# fc_rocket.net
KiCad netlist of a schematic drawn in EAGLE
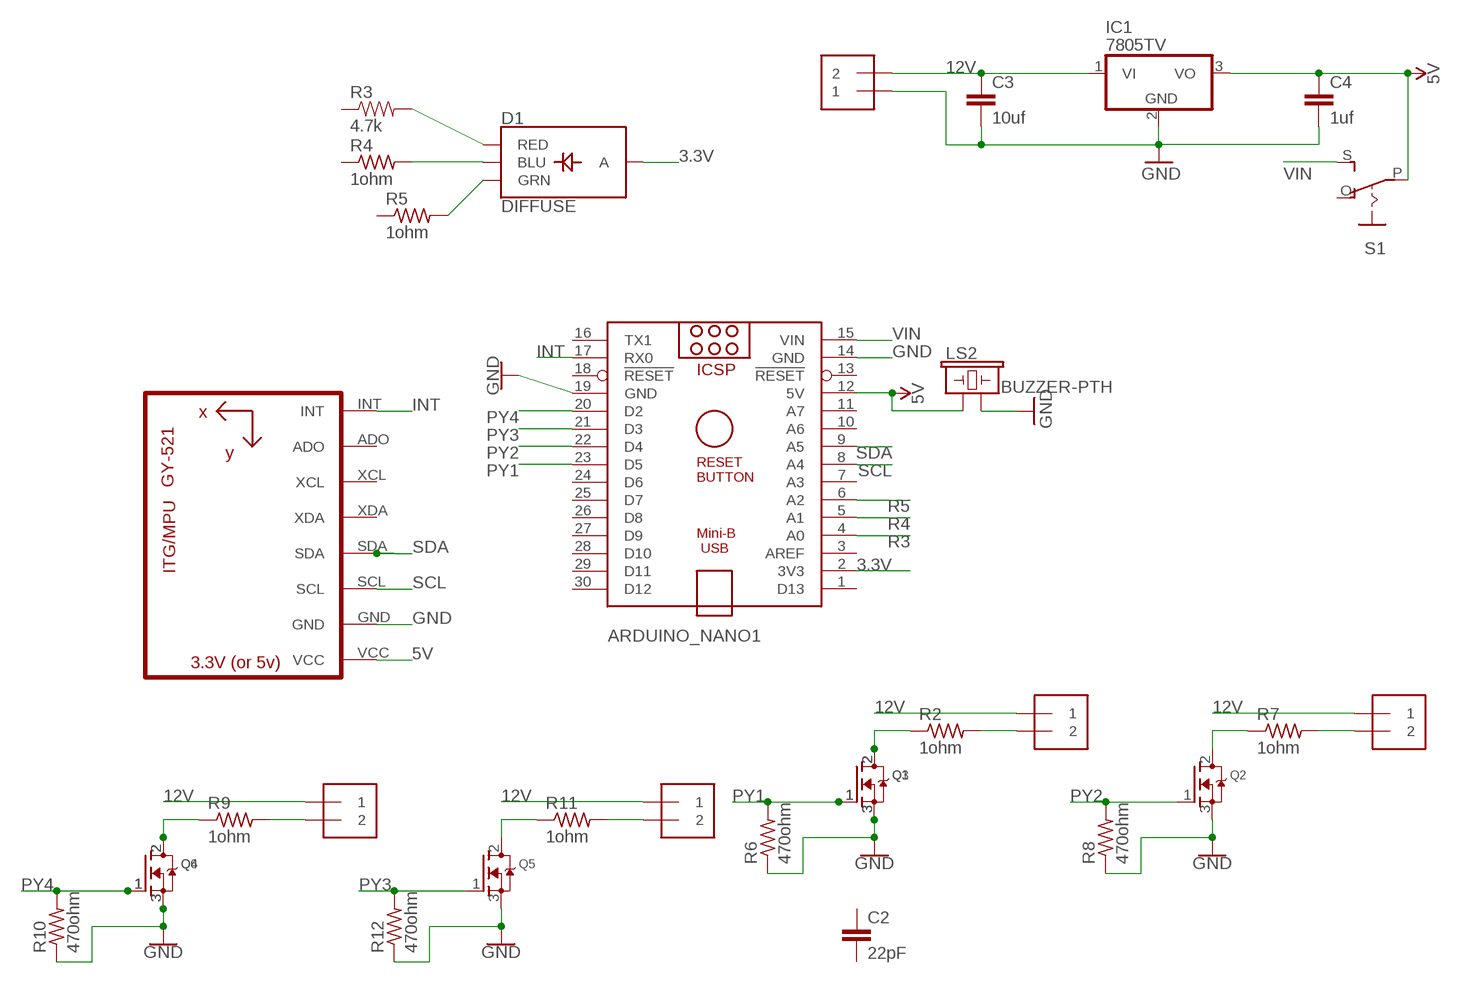
[diagram p0: schematic, sheet 1]

(export (version "E")
  (design (tool "Eeschema 10.0.6"))
  (components
    (comp (ref "ARDUINO_NANO1")
      (value "ARDUINO_NANO")
      (footprint "eagle-import:ARDUINO_NANO")
      (libsource (lib "eagle-import") (part "ARDUINO_NANO"))
    )
    (comp (ref "C2")
      (value "22pF")
      (footprint "eagle-import:CAP-PTH-2.54")
      (libsource (lib "eagle-import") (part "22PF-PTH-2.54MM-200V-5%"))
    )
    (comp (ref "C3")
      (value "10uf")
      (footprint "eagle-import:CAP-PTH-2.54")
      (libsource (lib "eagle-import") (part "22PF-PTH-2.54MM-200V-5%"))
    )
    (comp (ref "C4")
      (value "1uf")
      (footprint "eagle-import:CAP-PTH-2.54")
      (libsource (lib "eagle-import") (part "22PF-PTH-2.54MM-200V-5%"))
    )
    (comp (ref "D1")
      (value "DIFFUSE")
      (footprint "eagle-import:LED-RGB-THRU")
      (libsource (lib "eagle-import") (part "LED-RGB-CADIFFUSE"))
    )
    (comp (ref "IC1")
      (value "7805TV")
      (footprint "eagle-import:TO220V")
      (libsource (lib "eagle-import") (part "78TV05"))
    )
    (comp (ref "J2")
      (value "1X2-3.5MM")
      (footprint "eagle-import:1X2-3.5MM")
      (libsource (lib "eagle-import") (part "1X2-3.5MM"))
    )
    (comp (ref "J3")
      (value "1X2-3.5MM")
      (footprint "eagle-import:1X2-3.5MM")
      (libsource (lib "eagle-import") (part "1X2-3.5MM"))
    )
    (comp (ref "J4")
      (value "1X2-3.5MM")
      (footprint "eagle-import:1X2-3.5MM")
      (libsource (lib "eagle-import") (part "1X2-3.5MM"))
    )
    (comp (ref "J5")
      (value "1X2-3.5MM")
      (footprint "eagle-import:1X2-3.5MM")
      (libsource (lib "eagle-import") (part "1X2-3.5MM"))
    )
    (comp (ref "J6")
      (value "1X2-3.5MM")
      (footprint "eagle-import:1X2-3.5MM")
      (libsource (lib "eagle-import") (part "1X2-3.5MM"))
    )
    (comp (ref "LS2")
      (value "BUZZER-PTH")
      (footprint "eagle-import:BUZZER-12MM")
      (libsource (lib "eagle-import") (part "BUZZER-PTH"))
    )
    (comp (ref "Q1")
      (value "MOSFET-NGDS_TO220V")
      (footprint "eagle-import:TO220V")
      (libsource (lib "eagle-import") (part "MOSFET-NGDS_TO220V"))
    )
    (comp (ref "Q2")
      (value "MOSFET-NGDS_TO220V")
      (footprint "eagle-import:TO220V")
      (libsource (lib "eagle-import") (part "MOSFET-NGDS_TO220V"))
    )
    (comp (ref "Q3")
      (value "MOSFET-NGDS_TO220V")
      (footprint "eagle-import:TO220V")
      (libsource (lib "eagle-import") (part "MOSFET-NGDS_TO220V"))
    )
    (comp (ref "Q4")
      (value "MOSFET-NGDS_TO220V")
      (footprint "eagle-import:TO220V")
      (libsource (lib "eagle-import") (part "MOSFET-NGDS_TO220V"))
    )
    (comp (ref "Q5")
      (value "MOSFET-NGDS_TO220V")
      (footprint "eagle-import:TO220V")
      (libsource (lib "eagle-import") (part "MOSFET-NGDS_TO220V"))
    )
    (comp (ref "Q6")
      (value "MOSFET-NGDS_TO220V")
      (footprint "eagle-import:TO220V")
      (libsource (lib "eagle-import") (part "MOSFET-NGDS_TO220V"))
    )
    (comp (ref "R2")
      (value "1ohm")
      (footprint "eagle-import:0805-THM")
      (libsource (lib "eagle-import") (part "FLIPFLOP-RES"))
    )
    (comp (ref "R3")
      (value "4.7k")
      (footprint "eagle-import:0603")
      (libsource (lib "eagle-import") (part "4.7KOHM-0603-1/10W-1%"))
    )
    (comp (ref "R4")
      (value "1ohm")
      (footprint "eagle-import:0805-THM")
      (libsource (lib "eagle-import") (part "FLIPFLOP-RES"))
    )
    (comp (ref "R5")
      (value "1ohm")
      (footprint "eagle-import:0805-THM")
      (libsource (lib "eagle-import") (part "FLIPFLOP-RES"))
    )
    (comp (ref "R6")
      (value "470ohm")
      (footprint "eagle-import:0805-THM")
      (libsource (lib "eagle-import") (part "FLIPFLOP-RES"))
    )
    (comp (ref "R7")
      (value "1ohm")
      (footprint "eagle-import:0805-THM")
      (libsource (lib "eagle-import") (part "FLIPFLOP-RES"))
    )
    (comp (ref "R8")
      (value "470ohm")
      (footprint "eagle-import:0805-THM")
      (libsource (lib "eagle-import") (part "FLIPFLOP-RES"))
    )
    (comp (ref "R9")
      (value "1ohm")
      (footprint "eagle-import:0805-THM")
      (libsource (lib "eagle-import") (part "FLIPFLOP-RES"))
    )
    (comp (ref "R10")
      (value "470ohm")
      (footprint "eagle-import:0805-THM")
      (libsource (lib "eagle-import") (part "FLIPFLOP-RES"))
    )
    (comp (ref "R11")
      (value "1ohm")
      (footprint "eagle-import:0805-THM")
      (libsource (lib "eagle-import") (part "FLIPFLOP-RES"))
    )
    (comp (ref "R12")
      (value "470ohm")
      (footprint "eagle-import:0805-THM")
      (libsource (lib "eagle-import") (part "FLIPFLOP-RES"))
    )
    (comp (ref "S1")
      (value "EG1218S")
      (footprint "eagle-import:EG1218")
      (libsource (lib "eagle-import") (part "EG1218S"))
    )
    (comp (ref "U2")
      (value "GY-521MPU6050")
      (footprint "eagle-import:GY-521")
      (libsource (lib "eagle-import") (part "GY-521MPU6050"))
    )
  )
  (nets
    (net (code "1") (name "/3.3V") (class "Default")
      (node (ref "ARDUINO_NANO1") (pin "2") (pinfunction "3V3_2") (pintype "output"))
      (node (ref "D1") (pin "2") (pinfunction "A_2") (pintype "bidirectional"))
    )
    (net (code "2") (name "/12V") (class "Default")
      (node (ref "C3") (pin "1") (pinfunction "1_1") (pintype "passive"))
      (node (ref "IC1") (pin "1") (pinfunction "VI_1") (pintype "input"))
      (node (ref "J2") (pin "2") (pinfunction "2_2") (pintype "passive"))
      (node (ref "J3") (pin "1") (pinfunction "1_1") (pintype "passive"))
      (node (ref "J4") (pin "1") (pinfunction "1_1") (pintype "passive"))
      (node (ref "J5") (pin "1") (pinfunction "1_1") (pintype "passive"))
      (node (ref "J6") (pin "1") (pinfunction "1_1") (pintype "passive"))
    )
    (net (code "3") (name "/INT") (class "Default")
      (node (ref "ARDUINO_NANO1") (pin "17") (pinfunction "RX0_17") (pintype "bidirectional"))
      (node (ref "U2") (pin "INT") (pinfunction "INT_INT") (pintype "bidirectional"))
    )
    (net (code "4") (name "/PY1") (class "Default")
      (node (ref "ARDUINO_NANO1") (pin "23") (pinfunction "D5_23") (pintype "bidirectional"))
      (node (ref "Q1") (pin "1") (pinfunction "G_1") (pintype "bidirectional"))
      (node (ref "Q3") (pin "1") (pinfunction "G_1") (pintype "bidirectional"))
      (node (ref "R6") (pin "2") (pinfunction "2_2") (pintype "passive"))
    )
    (net (code "5") (name "/PY2") (class "Default")
      (node (ref "ARDUINO_NANO1") (pin "22") (pinfunction "D4_22") (pintype "bidirectional"))
      (node (ref "Q2") (pin "1") (pinfunction "G_1") (pintype "bidirectional"))
      (node (ref "R8") (pin "2") (pinfunction "2_2") (pintype "passive"))
    )
    (net (code "6") (name "/PY3") (class "Default")
      (node (ref "ARDUINO_NANO1") (pin "21") (pinfunction "D3_21") (pintype "bidirectional"))
      (node (ref "Q5") (pin "1") (pinfunction "G_1") (pintype "bidirectional"))
      (node (ref "R12") (pin "2") (pinfunction "2_2") (pintype "passive"))
    )
    (net (code "7") (name "/PY4") (class "Default")
      (node (ref "ARDUINO_NANO1") (pin "20") (pinfunction "D2_20") (pintype "bidirectional"))
      (node (ref "Q4") (pin "1") (pinfunction "G_1") (pintype "bidirectional"))
      (node (ref "Q6") (pin "1") (pinfunction "G_1") (pintype "bidirectional"))
      (node (ref "R10") (pin "2") (pinfunction "2_2") (pintype "passive"))
    )
    (net (code "8") (name "/R3") (class "Default")
      (node (ref "ARDUINO_NANO1") (pin "4") (pinfunction "A0_4") (pintype "bidirectional"))
    )
    (net (code "9") (name "/R4") (class "Default")
      (node (ref "ARDUINO_NANO1") (pin "5") (pinfunction "A1_5") (pintype "bidirectional"))
    )
    (net (code "10") (name "/R5") (class "Default")
      (node (ref "ARDUINO_NANO1") (pin "6") (pinfunction "A2_6") (pintype "bidirectional"))
    )
    (net (code "11") (name "/SCL") (class "Default")
      (node (ref "ARDUINO_NANO1") (pin "8") (pinfunction "A4_8") (pintype "bidirectional"))
      (node (ref "U2") (pin "SCL") (pinfunction "SCL_SCL") (pintype "bidirectional"))
    )
    (net (code "12") (name "/SDA") (class "Default")
      (node (ref "ARDUINO_NANO1") (pin "9") (pinfunction "A5_9") (pintype "bidirectional"))
      (node (ref "U2") (pin "SDA") (pinfunction "SDA_SDA") (pintype "bidirectional"))
    )
    (net (code "13") (name "/VIN") (class "Default")
      (node (ref "ARDUINO_NANO1") (pin "15") (pinfunction "VIN_15") (pintype "power_in"))
      (node (ref "S1") (pin "S") (pinfunction "S_S") (pintype "passive"))
    )
    (net (code "14") (name "5V") (class "Default")
      (node (ref "ARDUINO_NANO1") (pin "12") (pinfunction "5V_12") (pintype "power_in"))
      (node (ref "C4") (pin "1") (pinfunction "1_1") (pintype "passive"))
      (node (ref "IC1") (pin "3") (pinfunction "VO_3") (pintype "passive"))
      (node (ref "LS2") (pin "+") (pinfunction "1_+") (pintype "passive"))
      (node (ref "S1") (pin "P") (pinfunction "P_P") (pintype "passive"))
      (node (ref "U2") (pin "VCC") (pinfunction "VCC_VCC") (pintype "bidirectional"))
    )
    (net (code "15") (name "GND") (class "Default")
      (node (ref "ARDUINO_NANO1") (pin "14") (pinfunction "GND_14") (pintype "power_in"))
      (node (ref "ARDUINO_NANO1") (pin "19") (pinfunction "GND_19") (pintype "power_in"))
      (node (ref "C3") (pin "2") (pinfunction "2_2") (pintype "passive"))
      (node (ref "C4") (pin "2") (pinfunction "2_2") (pintype "passive"))
      (node (ref "IC1") (pin "2") (pinfunction "GND_2") (pintype "passive"))
      (node (ref "J2") (pin "1") (pinfunction "1_1") (pintype "passive"))
      (node (ref "LS2") (pin "-") (pinfunction "2_-") (pintype "passive"))
      (node (ref "Q1") (pin "3") (pinfunction "S_3") (pintype "bidirectional"))
      (node (ref "Q2") (pin "3") (pinfunction "S_3") (pintype "bidirectional"))
      (node (ref "Q3") (pin "3") (pinfunction "S_3") (pintype "bidirectional"))
      (node (ref "Q4") (pin "3") (pinfunction "S_3") (pintype "bidirectional"))
      (node (ref "Q5") (pin "3") (pinfunction "S_3") (pintype "bidirectional"))
      (node (ref "Q6") (pin "3") (pinfunction "S_3") (pintype "bidirectional"))
      (node (ref "R10") (pin "1") (pinfunction "1_1") (pintype "passive"))
      (node (ref "R12") (pin "1") (pinfunction "1_1") (pintype "passive"))
      (node (ref "R6") (pin "1") (pinfunction "1_1") (pintype "passive"))
      (node (ref "R8") (pin "1") (pinfunction "1_1") (pintype "passive"))
      (node (ref "U2") (pin "GND") (pinfunction "GND_GND") (pintype "bidirectional"))
    )
    (net (code "16") (name "Net-(D1-BLU)") (class "Default")
      (node (ref "D1") (pin "4") (pinfunction "BLU_4") (pintype "bidirectional"))
      (node (ref "R4") (pin "2") (pinfunction "2_2") (pintype "passive"))
    )
    (net (code "17") (name "Net-(D1-GRN)") (class "Default")
      (node (ref "D1") (pin "3") (pinfunction "GRN_3") (pintype "bidirectional"))
      (node (ref "R5") (pin "2") (pinfunction "2_2") (pintype "passive"))
    )
    (net (code "18") (name "Net-(D1-RED)") (class "Default")
      (node (ref "D1") (pin "1") (pinfunction "RED_1") (pintype "bidirectional"))
      (node (ref "R3") (pin "2") (pinfunction "2_2") (pintype "passive"))
    )
    (net (code "19") (name "Net-(J3-Pad2)") (class "Default")
      (node (ref "J3") (pin "2") (pinfunction "2_2") (pintype "passive"))
      (node (ref "R2") (pin "2") (pinfunction "2_2") (pintype "passive"))
    )
    (net (code "20") (name "Net-(J4-Pad2)") (class "Default")
      (node (ref "J4") (pin "2") (pinfunction "2_2") (pintype "passive"))
      (node (ref "R7") (pin "2") (pinfunction "2_2") (pintype "passive"))
    )
    (net (code "21") (name "Net-(J5-Pad2)") (class "Default")
      (node (ref "J5") (pin "2") (pinfunction "2_2") (pintype "passive"))
      (node (ref "R9") (pin "2") (pinfunction "2_2") (pintype "passive"))
    )
    (net (code "22") (name "Net-(J6-Pad2)") (class "Default")
      (node (ref "J6") (pin "2") (pinfunction "2_2") (pintype "passive"))
      (node (ref "R11") (pin "2") (pinfunction "2_2") (pintype "passive"))
    )
    (net (code "23") (name "Net-(Q1-D)") (class "Default")
      (node (ref "Q1") (pin "2") (pinfunction "D_2") (pintype "bidirectional"))
      (node (ref "Q3") (pin "2") (pinfunction "D_2") (pintype "bidirectional"))
      (node (ref "R2") (pin "1") (pinfunction "1_1") (pintype "passive"))
    )
    (net (code "24") (name "Net-(Q2-D)") (class "Default")
      (node (ref "Q2") (pin "2") (pinfunction "D_2") (pintype "bidirectional"))
      (node (ref "R7") (pin "1") (pinfunction "1_1") (pintype "passive"))
    )
    (net (code "25") (name "Net-(Q4-D)") (class "Default")
      (node (ref "Q4") (pin "2") (pinfunction "D_2") (pintype "bidirectional"))
      (node (ref "Q6") (pin "2") (pinfunction "D_2") (pintype "bidirectional"))
      (node (ref "R9") (pin "1") (pinfunction "1_1") (pintype "passive"))
    )
    (net (code "26") (name "Net-(Q5-D)") (class "Default")
      (node (ref "Q5") (pin "2") (pinfunction "D_2") (pintype "bidirectional"))
      (node (ref "R11") (pin "1") (pinfunction "1_1") (pintype "passive"))
    )
    (net (code "27") (name "unconnected-(ARDUINO_NANO1-A3-Pad7)") (class "Default")
      (node (ref "ARDUINO_NANO1") (pin "7") (pinfunction "A3_7") (pintype "bidirectional"))
    )
    (net (code "28") (name "unconnected-(ARDUINO_NANO1-A6-Pad10)") (class "Default")
      (node (ref "ARDUINO_NANO1") (pin "10") (pinfunction "A6_10") (pintype "bidirectional"))
    )
    (net (code "29") (name "unconnected-(ARDUINO_NANO1-A7-Pad11)") (class "Default")
      (node (ref "ARDUINO_NANO1") (pin "11") (pinfunction "A7_11") (pintype "bidirectional"))
    )
    (net (code "30") (name "unconnected-(ARDUINO_NANO1-AREF-Pad3)") (class "Default")
      (node (ref "ARDUINO_NANO1") (pin "3") (pinfunction "AREF_3") (pintype "input"))
    )
    (net (code "31") (name "unconnected-(ARDUINO_NANO1-D6-Pad24)") (class "Default")
      (node (ref "ARDUINO_NANO1") (pin "24") (pinfunction "D6_24") (pintype "bidirectional"))
    )
    (net (code "32") (name "unconnected-(ARDUINO_NANO1-D7-Pad25)") (class "Default")
      (node (ref "ARDUINO_NANO1") (pin "25") (pinfunction "D7_25") (pintype "bidirectional"))
    )
    (net (code "33") (name "unconnected-(ARDUINO_NANO1-D8-Pad26)") (class "Default")
      (node (ref "ARDUINO_NANO1") (pin "26") (pinfunction "D8_26") (pintype "bidirectional"))
    )
    (net (code "34") (name "unconnected-(ARDUINO_NANO1-D9-Pad27)") (class "Default")
      (node (ref "ARDUINO_NANO1") (pin "27") (pinfunction "D9_27") (pintype "bidirectional"))
    )
    (net (code "35") (name "unconnected-(ARDUINO_NANO1-D10-Pad28)") (class "Default")
      (node (ref "ARDUINO_NANO1") (pin "28") (pinfunction "D10_28") (pintype "bidirectional"))
    )
    (net (code "36") (name "unconnected-(ARDUINO_NANO1-D11-Pad29)") (class "Default")
      (node (ref "ARDUINO_NANO1") (pin "29") (pinfunction "D11_29") (pintype "bidirectional"))
    )
    (net (code "37") (name "unconnected-(ARDUINO_NANO1-D12-Pad30)") (class "Default")
      (node (ref "ARDUINO_NANO1") (pin "30") (pinfunction "D12_30") (pintype "bidirectional"))
    )
    (net (code "38") (name "unconnected-(ARDUINO_NANO1-D13-Pad1)") (class "Default")
      (node (ref "ARDUINO_NANO1") (pin "1") (pinfunction "D13_1") (pintype "bidirectional"))
    )
    (net (code "39") (name "unconnected-(ARDUINO_NANO1-TX1-Pad16)") (class "Default")
      (node (ref "ARDUINO_NANO1") (pin "16") (pinfunction "TX1_16") (pintype "bidirectional"))
    )
    (net (code "40") (name "unconnected-(ARDUINO_NANO1-~{RESET}-Pad13)") (class "Default")
      (node (ref "ARDUINO_NANO1") (pin "13") (pinfunction "~{RESET}_13") (pintype "input"))
    )
    (net (code "41") (name "unconnected-(ARDUINO_NANO1-~{RESET}-Pad18)") (class "Default")
      (node (ref "ARDUINO_NANO1") (pin "18") (pinfunction "~{RESET}_18") (pintype "input"))
    )
    (net (code "42") (name "unconnected-(C2-Pad1)") (class "Default")
      (node (ref "C2") (pin "1") (pinfunction "1_1") (pintype "passive"))
    )
    (net (code "43") (name "unconnected-(C2-Pad2)") (class "Default")
      (node (ref "C2") (pin "2") (pinfunction "2_2") (pintype "passive"))
    )
    (net (code "44") (name "unconnected-(R3-Pad1)") (class "Default")
      (node (ref "R3") (pin "1") (pinfunction "1_1") (pintype "passive"))
    )
    (net (code "45") (name "unconnected-(R4-Pad1)") (class "Default")
      (node (ref "R4") (pin "1") (pinfunction "1_1") (pintype "passive"))
    )
    (net (code "46") (name "unconnected-(R5-Pad1)") (class "Default")
      (node (ref "R5") (pin "1") (pinfunction "1_1") (pintype "passive"))
    )
    (net (code "47") (name "unconnected-(S1-PadO)") (class "Default")
      (node (ref "S1") (pin "O") (pinfunction "O_O") (pintype "passive"))
    )
    (net (code "48") (name "unconnected-(U2-PadADO)") (class "Default")
      (node (ref "U2") (pin "ADO") (pinfunction "ADO_ADO") (pintype "bidirectional"))
    )
    (net (code "49") (name "unconnected-(U2-PadXCL)") (class "Default")
      (node (ref "U2") (pin "XCL") (pinfunction "XCL_XCL") (pintype "bidirectional"))
    )
    (net (code "50") (name "unconnected-(U2-PadXDA)") (class "Default")
      (node (ref "U2") (pin "XDA") (pinfunction "XDA_XDA") (pintype "bidirectional"))
    )
  )
)
